# Dogfish3D_-_Thermistor_Channel.net
KiCad netlist of a schematic drawn in Altium Designer
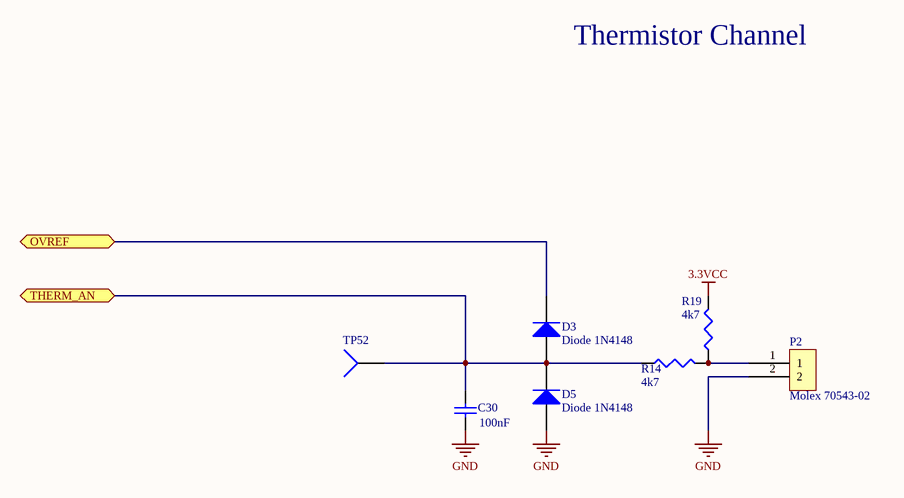
[diagram p0: Dogfish3D - Thermistor Channel.SchDoc]

(export (version "E")
  (design (tool "Eeschema 10.0.6"))
  (components
    (comp (ref "C30")
      (value "100nF")
      (footprint "1608[0603]")
      (description "Capacitor (Semiconductor SIM Model)")
      (fields (field (name "Comment") "Cap Semi") (field (name "PUBLISHER") "Altium Limited"))
      (libsource (lib "Miscellaneous Devices") (part "Cap Semi"))
    )
    (comp (ref "D3")
      (value "Diode 1N4148")
      (footprint "1N4148WT")
      (description "High Conductance Fast Diode")
      (fields (field (name "PUBLISHER") "Altium Limited"))
      (libsource (lib "Miscellaneous Devices") (part "Diode 1N4148"))
    )
    (comp (ref "D5")
      (value "Diode 1N4148")
      (footprint "1N4148WT")
      (description "High Conductance Fast Diode")
      (fields (field (name "PUBLISHER") "Altium Limited"))
      (libsource (lib "Miscellaneous Devices") (part "Diode 1N4148"))
    )
    (comp (ref "P2")
      (value "Molex 70543-02")
      (footprint "70543-02")
      (libsource (lib "ZMBo Schematic Library") (part "Molex 70543-02"))
    )
    (comp (ref "R14")
      (value "4k7")
      (footprint "J1-0603")
      (description "Resistor")
      (fields (field (name "Comment") "Res3") (field (name "PUBLISHER") "Altium Limited"))
      (libsource (lib "Miscellaneous Devices") (part "Res3"))
    )
    (comp (ref "R19")
      (value "4k7")
      (footprint "J1-0603")
      (description "Resistor")
      (fields (field (name "Comment") "Res3") (field (name "PUBLISHER") "Altium Limited"))
      (libsource (lib "Miscellaneous Devices") (part "Res3"))
    )
    (comp (ref "TP52")
      (value "TP4")
      (footprint "TP-2")
      (description "Socket")
      (fields (field (name "PUBLISHER") "Altium Limited"))
      (libsource (lib "ZMBo Schematic Library") (part "Socket"))
    )
  )
  (nets
    (net (code "1") (name "/OVREF") (class "Default")
      (node (ref "D3") (pin "2") (pinfunction "K_2") (pintype "passive"))
    )
    (net (code "2") (name "/THERM_AN") (class "Default")
      (node (ref "C30") (pin "2") (pinfunction "2_2") (pintype "passive"))
      (node (ref "D3") (pin "1") (pinfunction "A_1") (pintype "passive"))
      (node (ref "D5") (pin "2") (pinfunction "K_2") (pintype "passive"))
      (node (ref "R14") (pin "1") (pinfunction "1_1") (pintype "passive"))
      (node (ref "TP52") (pin "1") (pinfunction "1_1") (pintype "passive"))
    )
    (net (code "3") (name "3.3VCC") (class "Default")
      (node (ref "R19") (pin "2") (pinfunction "2_2") (pintype "passive"))
    )
    (net (code "4") (name "GND") (class "Default")
      (node (ref "C30") (pin "1") (pinfunction "1_1") (pintype "passive"))
      (node (ref "D5") (pin "1") (pinfunction "A_1") (pintype "passive"))
      (node (ref "P2") (pin "2") (pinfunction "2_2") (pintype "passive"))
    )
    (net (code "5") (name "Net-(P2-Pad1)") (class "Default")
      (node (ref "P2") (pin "1") (pinfunction "1_1") (pintype "passive"))
      (node (ref "R14") (pin "2") (pinfunction "2_2") (pintype "passive"))
      (node (ref "R19") (pin "1") (pinfunction "1_1") (pintype "passive"))
    )
  )
)
